# WirelessTransceiverUSB_RevA.net
KiCad netlist of a schematic drawn in EAGLE
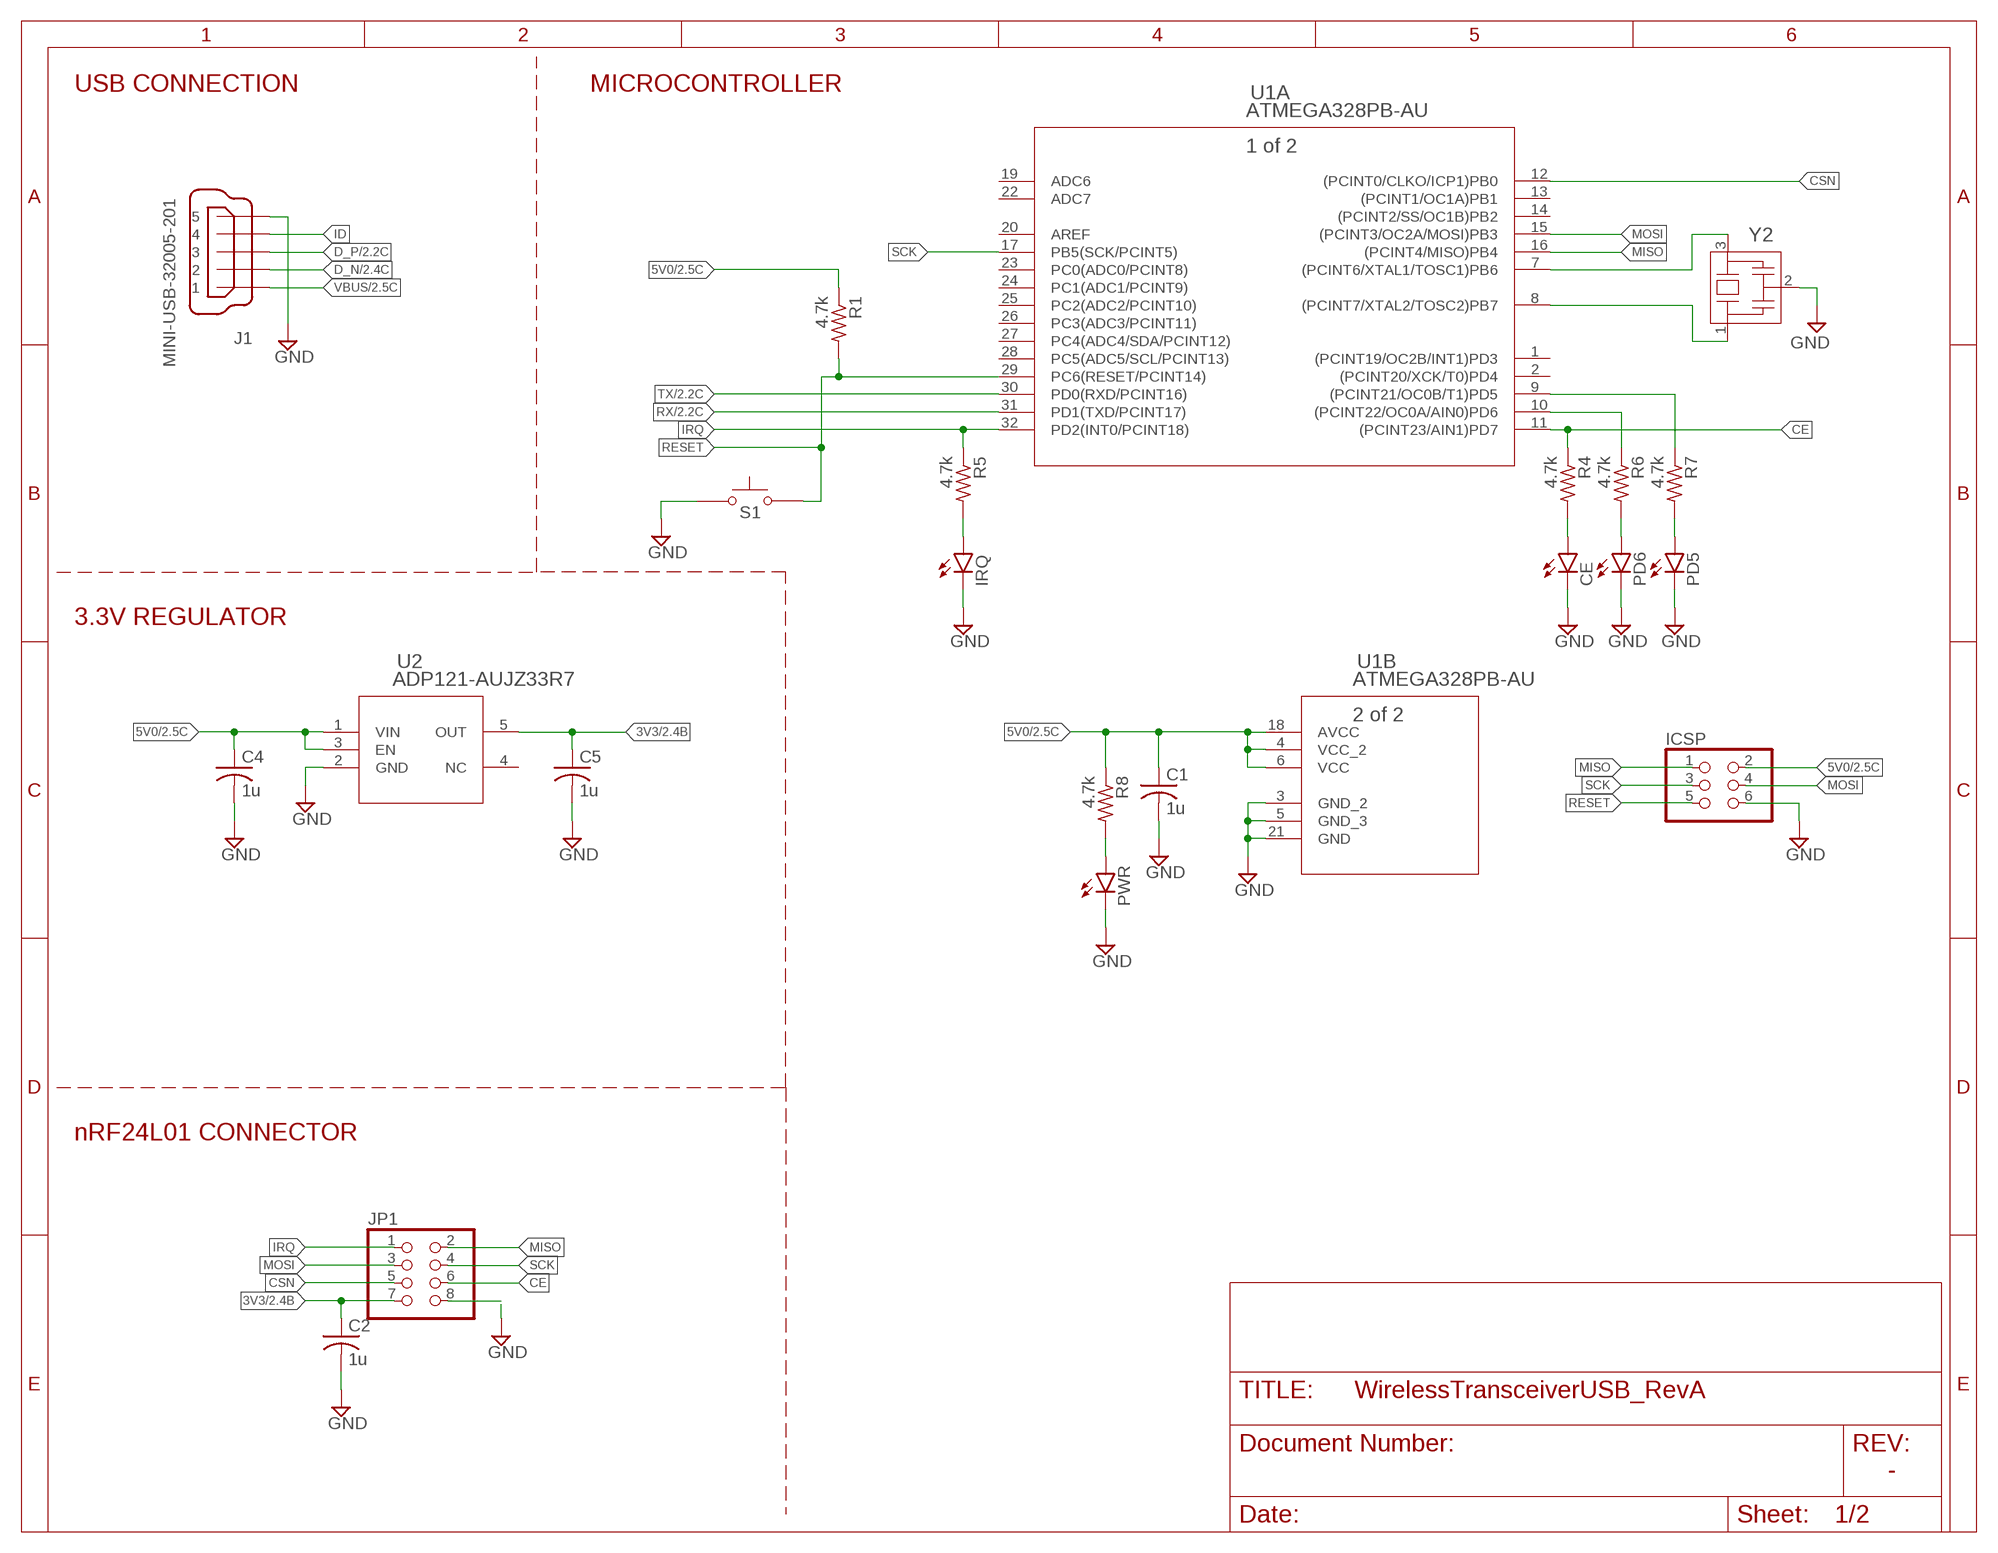
[diagram p0: schematic, sheet 1]
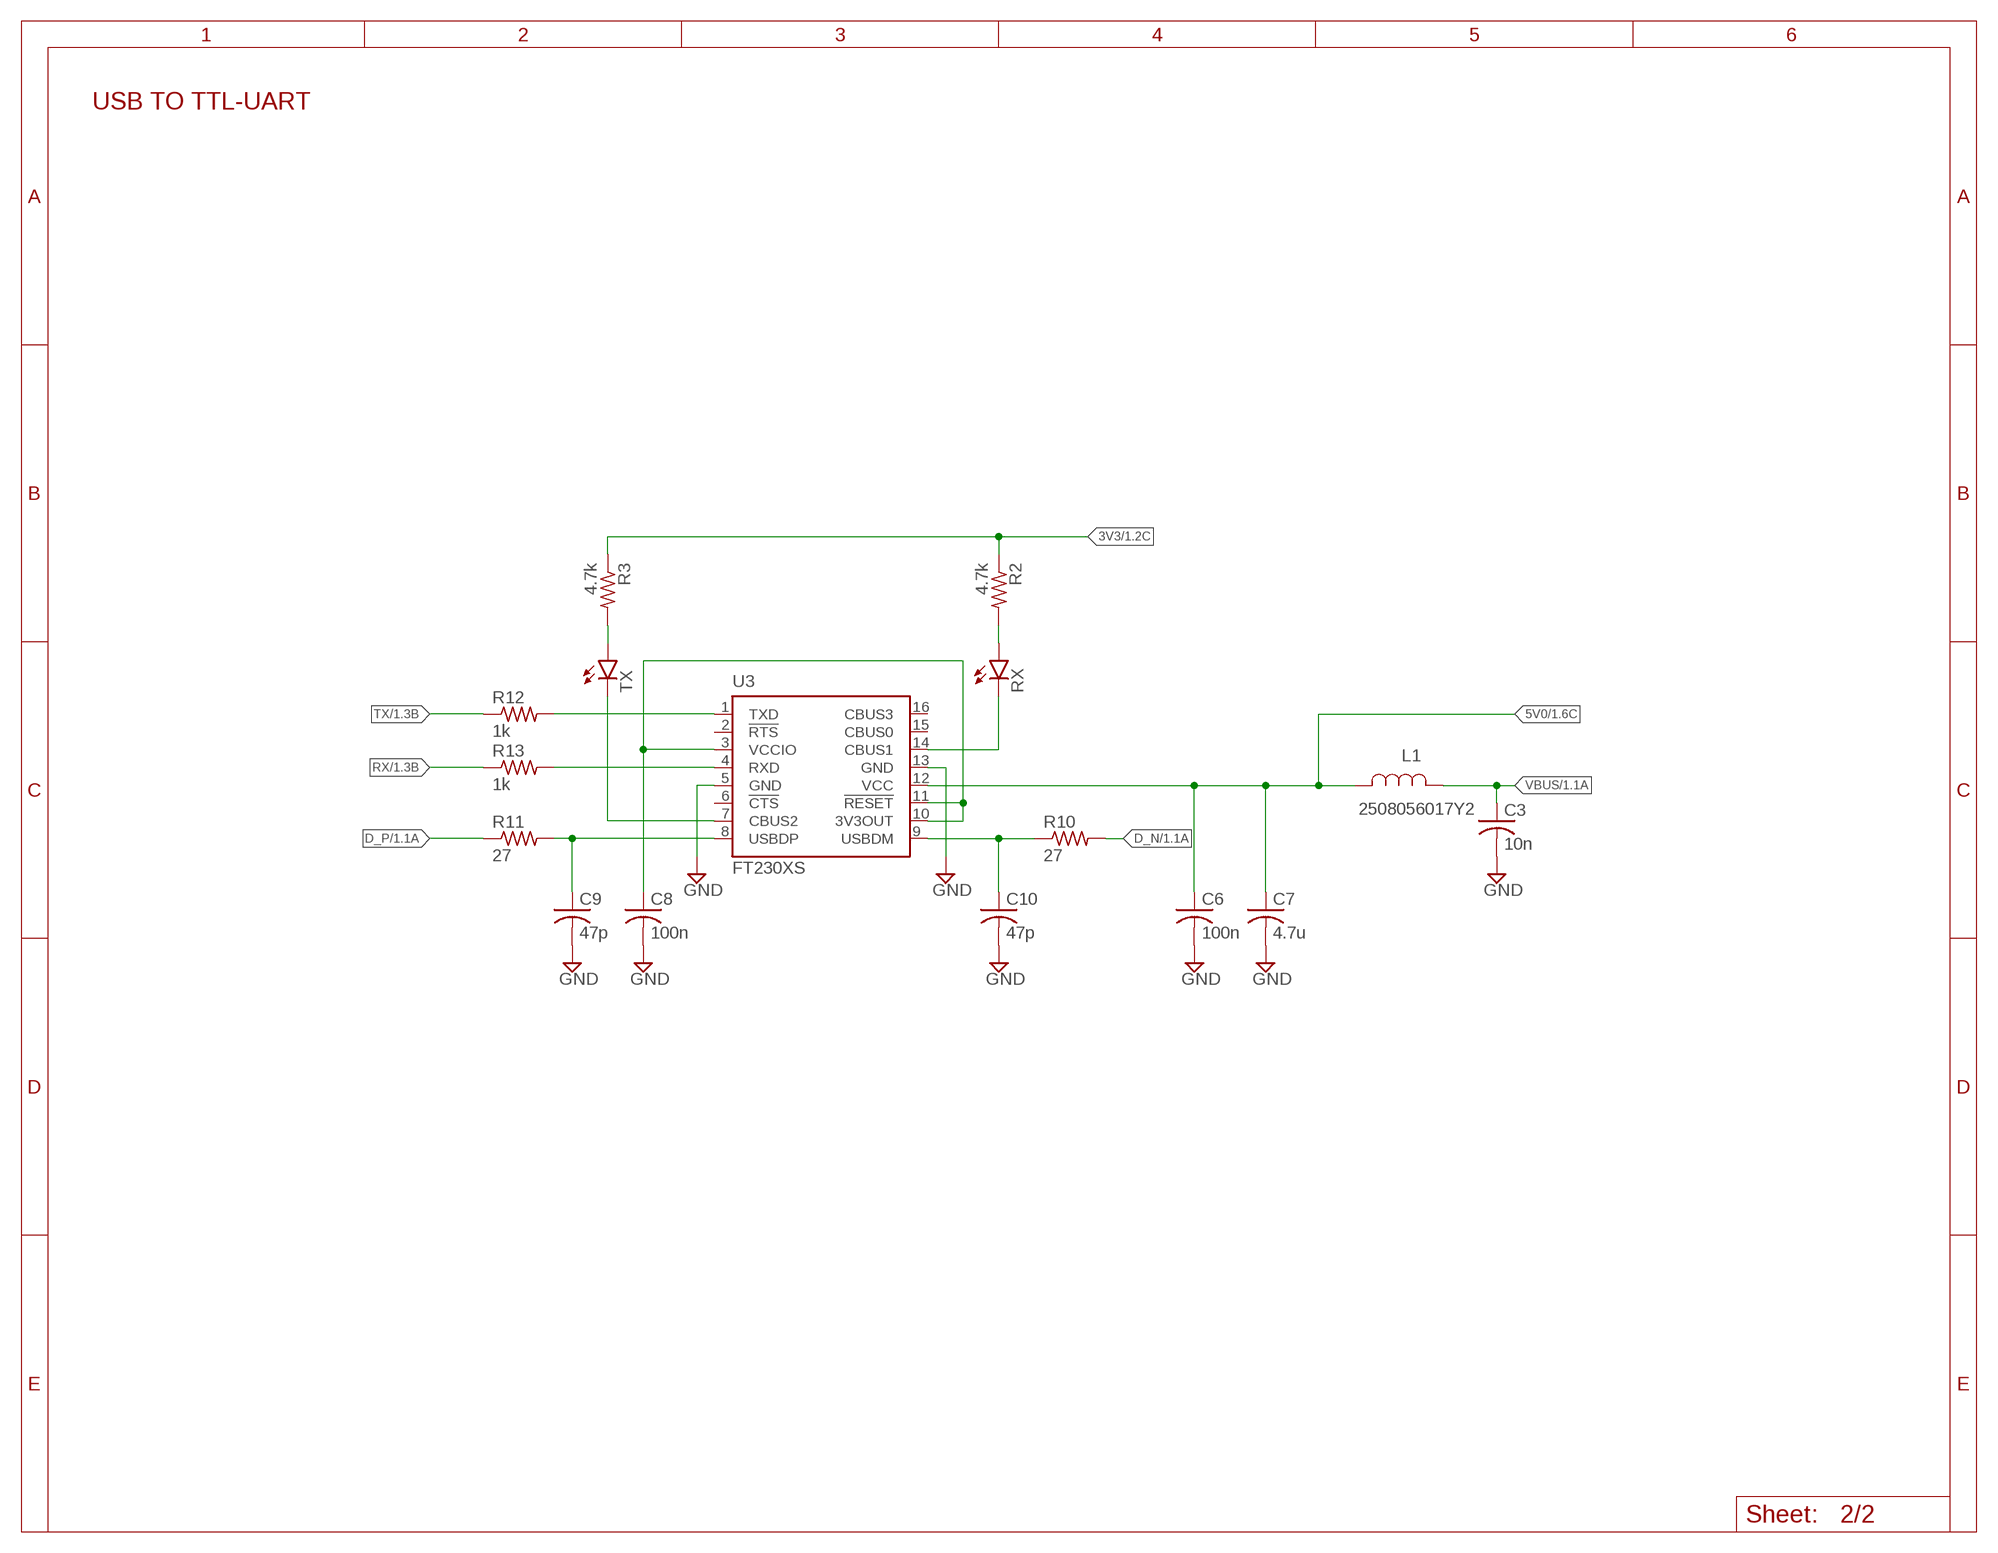
[diagram p1: schematic, sheet 2]

(export (version "E")
  (design (tool "Eeschema 10.0.6"))
  (components
    (comp (ref "C1")
      (value "1u")
      (footprint "eagle-import:C0805")
      (libsource (lib "eagle-import") (part "C-USC0805"))
    )
    (comp (ref "C2")
      (value "1u")
      (footprint "eagle-import:C0805")
      (libsource (lib "eagle-import") (part "C-USC0805"))
    )
    (comp (ref "C4")
      (value "1u")
      (footprint "eagle-import:C0805")
      (libsource (lib "eagle-import") (part "C-USC0805"))
    )
    (comp (ref "C5")
      (value "1u")
      (footprint "eagle-import:C0805")
      (libsource (lib "eagle-import") (part "C-USC0805"))
    )
    (comp (ref "CE")
      (value "LEDSML0805")
      (footprint "eagle-import:SML0805")
      (libsource (lib "eagle-import") (part "LEDSML0805"))
    )
    (comp (ref "ICSP")
      (value "PINHD-2X3")
      (footprint "eagle-import:2X03")
      (libsource (lib "eagle-import") (part "PINHD-2X3"))
    )
    (comp (ref "IRQ")
      (value "LEDSML0805")
      (footprint "eagle-import:SML0805")
      (libsource (lib "eagle-import") (part "LEDSML0805"))
    )
    (comp (ref "J1")
      (value "MINI-USB-32005-201")
      (footprint "eagle-import:32005-201")
      (libsource (lib "eagle-import") (part "MINI-USB-32005-201"))
    )
    (comp (ref "JP1")
      (value "PINHD-2X4")
      (footprint "eagle-import:2X04")
      (libsource (lib "eagle-import") (part "PINHD-2X4"))
    )
    (comp (ref "PD5")
      (value "LEDSML0805")
      (footprint "eagle-import:SML0805")
      (libsource (lib "eagle-import") (part "LEDSML0805"))
    )
    (comp (ref "PD6")
      (value "LEDSML0805")
      (footprint "eagle-import:SML0805")
      (libsource (lib "eagle-import") (part "LEDSML0805"))
    )
    (comp (ref "PWR")
      (value "LEDSML0805")
      (footprint "eagle-import:SML0805")
      (libsource (lib "eagle-import") (part "LEDSML0805"))
    )
    (comp (ref "R1")
      (value "4.7k")
      (footprint "eagle-import:R0805")
      (libsource (lib "eagle-import") (part "R-US_R0805"))
    )
    (comp (ref "R4")
      (value "4.7k")
      (footprint "eagle-import:R0805")
      (libsource (lib "eagle-import") (part "R-US_R0805"))
    )
    (comp (ref "R5")
      (value "4.7k")
      (footprint "eagle-import:R0805")
      (libsource (lib "eagle-import") (part "R-US_R0805"))
    )
    (comp (ref "R6")
      (value "4.7k")
      (footprint "eagle-import:R0805")
      (libsource (lib "eagle-import") (part "R-US_R0805"))
    )
    (comp (ref "R7")
      (value "4.7k")
      (footprint "eagle-import:R0805")
      (libsource (lib "eagle-import") (part "R-US_R0805"))
    )
    (comp (ref "R8")
      (value "4.7k")
      (footprint "eagle-import:R0805")
      (libsource (lib "eagle-import") (part "R-US_R0805"))
    )
    (comp (ref "S1")
      (value "TL3315NF100Q")
      (footprint "eagle-import:SW_TL3315NF100Q")
      (fields (field (name "MF") "E-Switch"))
      (libsource (lib "eagle-import") (part "TL3315NF100Q"))
    )
    (comp (ref "U1")
      (value "ATMEGA328PB-AU")
      (footprint "eagle-import:32A_MCH")
      (fields (field (name "COPYRIGHT") "Copyright (C) 2023 Ultra Librarian. All rights reserved."))
      (libsource (lib "eagle-import") (part "ATMEGA328PB-AU"))
    )
    (comp (ref "U2")
      (value "ADP121-AUJZ33R7")
      (footprint "eagle-import:UJ_5_ADI")
      (fields (field (name "COPYRIGHT") "Copyright (C) 2023 Ultra Librarian. All rights reserved."))
      (libsource (lib "eagle-import") (part "ADP121-AUJZ33R7"))
    )
    (comp (ref "Y2")
      (value "CSTNE16M0V530000R0")
      (footprint "eagle-import:CSTNE16M0V530000R0_MUR")
      (fields (field (name "COPYRIGHT") "Copyright (C) 2023 Ultra Librarian. All rights reserved."))
      (libsource (lib "eagle-import") (part "CSTNE16M0V530000R0"))
    )
    (comp (ref "C3")
      (value "10n")
      (footprint "eagle-import:C0805")
      (libsource (lib "eagle-import") (part "C-USC0805"))
    )
    (comp (ref "C6")
      (value "100n")
      (footprint "eagle-import:C0805")
      (libsource (lib "eagle-import") (part "C-USC0805"))
    )
    (comp (ref "C7")
      (value "4.7u")
      (footprint "eagle-import:C0805")
      (libsource (lib "eagle-import") (part "C-USC0805"))
    )
    (comp (ref "C8")
      (value "100n")
      (footprint "eagle-import:C0805")
      (libsource (lib "eagle-import") (part "C-USC0805"))
    )
    (comp (ref "C9")
      (value "47p")
      (footprint "eagle-import:C0603")
      (libsource (lib "eagle-import") (part "C-USC0603"))
    )
    (comp (ref "C10")
      (value "47p")
      (footprint "eagle-import:C0603")
      (libsource (lib "eagle-import") (part "C-USC0603"))
    )
    (comp (ref "L1")
      (value "2508056017Y2")
      (footprint "eagle-import:IND_25_0805_FRT")
      (fields (field (name "COPYRIGHT") "Copyright (C) 2023 Ultra Librarian. All rights reserved."))
      (libsource (lib "eagle-import") (part "2508056017Y2"))
    )
    (comp (ref "R2")
      (value "4.7k")
      (footprint "eagle-import:R0805")
      (libsource (lib "eagle-import") (part "R-US_R0805"))
    )
    (comp (ref "R3")
      (value "4.7k")
      (footprint "eagle-import:R0805")
      (libsource (lib "eagle-import") (part "R-US_R0805"))
    )
    (comp (ref "R10")
      (value "27")
      (footprint "eagle-import:R0603")
      (libsource (lib "eagle-import") (part "R-US_R0603"))
    )
    (comp (ref "R11")
      (value "27")
      (footprint "eagle-import:R0603")
      (libsource (lib "eagle-import") (part "R-US_R0603"))
    )
    (comp (ref "R12")
      (value "1k")
      (footprint "eagle-import:R0805")
      (libsource (lib "eagle-import") (part "R-US_R0805"))
    )
    (comp (ref "R13")
      (value "1k")
      (footprint "eagle-import:R0805")
      (libsource (lib "eagle-import") (part "R-US_R0805"))
    )
    (comp (ref "RX")
      (value "LEDSML0805")
      (footprint "eagle-import:SML0805")
      (libsource (lib "eagle-import") (part "LEDSML0805"))
    )
    (comp (ref "TX")
      (value "LEDSML0805")
      (footprint "eagle-import:SML0805")
      (libsource (lib "eagle-import") (part "LEDSML0805"))
    )
    (comp (ref "U3")
      (value "FT230XS")
      (footprint "eagle-import:SSOP16")
      (libsource (lib "eagle-import") (part "FT230XS"))
    )
  )
  (nets
    (net (code "1") (name "3V3") (class "Default")
      (node (ref "C2") (pin "1") (pinfunction "1_1") (pintype "passive"))
      (node (ref "C5") (pin "1") (pinfunction "1_1") (pintype "passive"))
      (node (ref "JP1") (pin "7") (pinfunction "7_7") (pintype "passive"))
      (node (ref "R2") (pin "1") (pinfunction "1_1") (pintype "passive"))
      (node (ref "R3") (pin "1") (pinfunction "1_1") (pintype "passive"))
      (node (ref "U2") (pin "5") (pinfunction "OUT_5") (pintype "output"))
    )
    (net (code "2") (name "5V0") (class "Default")
      (node (ref "C1") (pin "1") (pinfunction "1_1") (pintype "passive"))
      (node (ref "C4") (pin "1") (pinfunction "1_1") (pintype "passive"))
      (node (ref "C6") (pin "1") (pinfunction "1_1") (pintype "passive"))
      (node (ref "C7") (pin "1") (pinfunction "1_1") (pintype "passive"))
      (node (ref "ICSP") (pin "2") (pinfunction "2_2") (pintype "passive"))
      (node (ref "L1") (pin "2") (pinfunction "2_2") (pintype "passive"))
      (node (ref "R1") (pin "1") (pinfunction "1_1") (pintype "passive"))
      (node (ref "R8") (pin "1") (pinfunction "1_1") (pintype "passive"))
      (node (ref "U1") (pin "18") (pinfunction "AVCC_18") (pintype "power_in"))
      (node (ref "U1") (pin "4") (pinfunction "VCC_2_4") (pintype "power_in"))
      (node (ref "U1") (pin "6") (pinfunction "VCC_6") (pintype "power_in"))
      (node (ref "U2") (pin "1") (pinfunction "VIN_1") (pintype "input"))
      (node (ref "U2") (pin "3") (pinfunction "EN_3") (pintype "input"))
      (node (ref "U3") (pin "12") (pinfunction "VCC_12") (pintype "power_in"))
    )
    (net (code "3") (name "CE") (class "Default")
      (node (ref "JP1") (pin "6") (pinfunction "6_6") (pintype "passive"))
      (node (ref "R4") (pin "1") (pinfunction "1_1") (pintype "passive"))
      (node (ref "U1") (pin "11") (pinfunction "(PCINT23/AIN1)PD7_11") (pintype "bidirectional"))
    )
    (net (code "4") (name "CSN") (class "Default")
      (node (ref "JP1") (pin "5") (pinfunction "5_5") (pintype "passive"))
      (node (ref "U1") (pin "12") (pinfunction "(PCINT0/CLKO/ICP1)PB0_12") (pintype "bidirectional"))
    )
    (net (code "5") (name "D_N") (class "Default")
      (node (ref "J1") (pin "2") (pinfunction "2_2") (pintype "passive"))
      (node (ref "R10") (pin "2") (pinfunction "2_2") (pintype "passive"))
    )
    (net (code "6") (name "D_P") (class "Default")
      (node (ref "J1") (pin "3") (pinfunction "3_3") (pintype "passive"))
      (node (ref "R11") (pin "1") (pinfunction "1_1") (pintype "passive"))
    )
    (net (code "7") (name "GND") (class "Default")
      (node (ref "C1") (pin "2") (pinfunction "2_2") (pintype "passive"))
      (node (ref "C10") (pin "2") (pinfunction "2_2") (pintype "passive"))
      (node (ref "C2") (pin "2") (pinfunction "2_2") (pintype "passive"))
      (node (ref "C3") (pin "2") (pinfunction "2_2") (pintype "passive"))
      (node (ref "C4") (pin "2") (pinfunction "2_2") (pintype "passive"))
      (node (ref "C5") (pin "2") (pinfunction "2_2") (pintype "passive"))
      (node (ref "C6") (pin "2") (pinfunction "2_2") (pintype "passive"))
      (node (ref "C7") (pin "2") (pinfunction "2_2") (pintype "passive"))
      (node (ref "C8") (pin "2") (pinfunction "2_2") (pintype "passive"))
      (node (ref "C9") (pin "2") (pinfunction "2_2") (pintype "passive"))
      (node (ref "CE") (pin "C") (pinfunction "C_C") (pintype "passive"))
      (node (ref "ICSP") (pin "6") (pinfunction "6_6") (pintype "passive"))
      (node (ref "IRQ") (pin "C") (pinfunction "C_C") (pintype "passive"))
      (node (ref "J1") (pin "5") (pinfunction "5_5") (pintype "passive"))
      (node (ref "JP1") (pin "8") (pinfunction "8_8") (pintype "passive"))
      (node (ref "PD5") (pin "C") (pinfunction "C_C") (pintype "passive"))
      (node (ref "PD6") (pin "C") (pinfunction "C_C") (pintype "passive"))
      (node (ref "PWR") (pin "C") (pinfunction "C_C") (pintype "passive"))
      (node (ref "S1") (pin "1") (pinfunction "1_1") (pintype "passive"))
      (node (ref "S1") (pin "2") (pinfunction "1_2") (pintype "passive"))
      (node (ref "U1") (pin "21") (pinfunction "GND_21") (pintype "power_in"))
      (node (ref "U1") (pin "3") (pinfunction "GND_2_3") (pintype "power_in"))
      (node (ref "U1") (pin "5") (pinfunction "GND_3_5") (pintype "power_in"))
      (node (ref "U2") (pin "2") (pinfunction "GND_2") (pintype "power_in"))
      (node (ref "U3") (pin "13") (pinfunction "GND_13") (pintype "power_in"))
      (node (ref "U3") (pin "5") (pinfunction "GND_5") (pintype "power_in"))
      (node (ref "Y2") (pin "2") (pinfunction "2_2") (pintype "passive"))
    )
    (net (code "8") (name "ID") (class "Default")
      (node (ref "J1") (pin "4") (pinfunction "4_4") (pintype "passive"))
    )
    (net (code "9") (name "IRQ") (class "Default")
      (node (ref "JP1") (pin "1") (pinfunction "1_1") (pintype "passive"))
      (node (ref "R5") (pin "1") (pinfunction "1_1") (pintype "passive"))
      (node (ref "U1") (pin "32") (pinfunction "PD2(INT0/PCINT18)_32") (pintype "bidirectional"))
    )
    (net (code "10") (name "MISO") (class "Default")
      (node (ref "ICSP") (pin "1") (pinfunction "1_1") (pintype "passive"))
      (node (ref "JP1") (pin "2") (pinfunction "2_2") (pintype "passive"))
      (node (ref "U1") (pin "16") (pinfunction "(PCINT4/MISO)PB4_16") (pintype "bidirectional"))
    )
    (net (code "11") (name "MOSI") (class "Default")
      (node (ref "ICSP") (pin "4") (pinfunction "4_4") (pintype "passive"))
      (node (ref "JP1") (pin "3") (pinfunction "3_3") (pintype "passive"))
      (node (ref "U1") (pin "15") (pinfunction "(PCINT3/OC2A/MOSI)PB3_15") (pintype "bidirectional"))
    )
    (net (code "12") (name "Net-(CE-PadA)") (class "Default")
      (node (ref "CE") (pin "A") (pinfunction "A_A") (pintype "passive"))
      (node (ref "R4") (pin "2") (pinfunction "2_2") (pintype "passive"))
    )
    (net (code "13") (name "Net-(IRQ-PadA)") (class "Default")
      (node (ref "IRQ") (pin "A") (pinfunction "A_A") (pintype "passive"))
      (node (ref "R5") (pin "2") (pinfunction "2_2") (pintype "passive"))
    )
    (net (code "14") (name "Net-(PD5-PadA)") (class "Default")
      (node (ref "PD5") (pin "A") (pinfunction "A_A") (pintype "passive"))
      (node (ref "R7") (pin "2") (pinfunction "2_2") (pintype "passive"))
    )
    (net (code "15") (name "Net-(PD6-PadA)") (class "Default")
      (node (ref "PD6") (pin "A") (pinfunction "A_A") (pintype "passive"))
      (node (ref "R6") (pin "2") (pinfunction "2_2") (pintype "passive"))
    )
    (net (code "16") (name "Net-(PWR-PadA)") (class "Default")
      (node (ref "PWR") (pin "A") (pinfunction "A_A") (pintype "passive"))
      (node (ref "R8") (pin "2") (pinfunction "2_2") (pintype "passive"))
    )
    (net (code "17") (name "Net-(R2-Pad2)") (class "Default")
      (node (ref "R2") (pin "2") (pinfunction "2_2") (pintype "passive"))
      (node (ref "RX") (pin "A") (pinfunction "A_A") (pintype "passive"))
    )
    (net (code "18") (name "Net-(R3-Pad2)") (class "Default")
      (node (ref "R3") (pin "2") (pinfunction "2_2") (pintype "passive"))
      (node (ref "TX") (pin "A") (pinfunction "A_A") (pintype "passive"))
    )
    (net (code "19") (name "Net-(U1A-(PCINT6{slash}XTAL1{slash}TOSC1)PB6)") (class "Default")
      (node (ref "U1") (pin "7") (pinfunction "(PCINT6/XTAL1/TOSC1)PB6_7") (pintype "bidirectional"))
      (node (ref "Y2") (pin "3") (pinfunction "3_3") (pintype "output"))
    )
    (net (code "20") (name "Net-(U1A-(PCINT7{slash}XTAL2{slash}TOSC2)PB7)") (class "Default")
      (node (ref "U1") (pin "8") (pinfunction "(PCINT7/XTAL2/TOSC2)PB7_8") (pintype "bidirectional"))
      (node (ref "Y2") (pin "1") (pinfunction "1_1") (pintype "input"))
    )
    (net (code "21") (name "Net-(U1A-(PCINT21{slash}OC0B{slash}T1)PD5)") (class "Default")
      (node (ref "R7") (pin "1") (pinfunction "1_1") (pintype "passive"))
      (node (ref "U1") (pin "9") (pinfunction "(PCINT21/OC0B/T1)PD5_9") (pintype "bidirectional"))
    )
    (net (code "22") (name "Net-(U1A-(PCINT22{slash}OC0A{slash}AIN0)PD6)") (class "Default")
      (node (ref "R6") (pin "1") (pinfunction "1_1") (pintype "passive"))
      (node (ref "U1") (pin "10") (pinfunction "(PCINT22/OC0A/AIN0)PD6_10") (pintype "bidirectional"))
    )
    (net (code "23") (name "Net-(U3-3V3OUT)") (class "Default")
      (node (ref "C8") (pin "1") (pinfunction "1_1") (pintype "passive"))
      (node (ref "U3") (pin "10") (pinfunction "3V3OUT_10") (pintype "output"))
      (node (ref "U3") (pin "11") (pinfunction "~{RESET}_11") (pintype "input"))
      (node (ref "U3") (pin "3") (pinfunction "VCCIO_3") (pintype "power_in"))
    )
    (net (code "24") (name "Net-(U3-CBUS1)") (class "Default")
      (node (ref "RX") (pin "C") (pinfunction "C_C") (pintype "passive"))
      (node (ref "U3") (pin "14") (pinfunction "CBUS1_14") (pintype "bidirectional"))
    )
    (net (code "25") (name "Net-(U3-CBUS2)") (class "Default")
      (node (ref "TX") (pin "C") (pinfunction "C_C") (pintype "passive"))
      (node (ref "U3") (pin "7") (pinfunction "CBUS2_7") (pintype "bidirectional"))
    )
    (net (code "26") (name "Net-(U3-RXD)") (class "Default")
      (node (ref "R13") (pin "2") (pinfunction "2_2") (pintype "passive"))
      (node (ref "U3") (pin "4") (pinfunction "RXD_4") (pintype "input"))
    )
    (net (code "27") (name "Net-(U3-TXD)") (class "Default")
      (node (ref "R12") (pin "2") (pinfunction "2_2") (pintype "passive"))
      (node (ref "U3") (pin "1") (pinfunction "TXD_1") (pintype "output"))
    )
    (net (code "28") (name "Net-(U3-USBDM)") (class "Default")
      (node (ref "C10") (pin "1") (pinfunction "1_1") (pintype "passive"))
      (node (ref "R10") (pin "1") (pinfunction "1_1") (pintype "passive"))
      (node (ref "U3") (pin "9") (pinfunction "USBDM_9") (pintype "input"))
    )
    (net (code "29") (name "Net-(U3-USBDP)") (class "Default")
      (node (ref "C9") (pin "1") (pinfunction "1_1") (pintype "passive"))
      (node (ref "R11") (pin "2") (pinfunction "2_2") (pintype "passive"))
      (node (ref "U3") (pin "8") (pinfunction "USBDP_8") (pintype "input"))
    )
    (net (code "30") (name "RESET") (class "Default")
      (node (ref "ICSP") (pin "5") (pinfunction "5_5") (pintype "passive"))
      (node (ref "R1") (pin "2") (pinfunction "2_2") (pintype "passive"))
      (node (ref "S1") (pin "3") (pinfunction "3_3") (pintype "passive"))
      (node (ref "S1") (pin "4") (pinfunction "3_4") (pintype "passive"))
      (node (ref "U1") (pin "29") (pinfunction "PC6(RESET/PCINT14)_29") (pintype "bidirectional"))
    )
    (net (code "31") (name "RX") (class "Default")
      (node (ref "R13") (pin "1") (pinfunction "1_1") (pintype "passive"))
      (node (ref "U1") (pin "31") (pinfunction "PD1(TXD/PCINT17)_31") (pintype "bidirectional"))
    )
    (net (code "32") (name "SCK") (class "Default")
      (node (ref "ICSP") (pin "3") (pinfunction "3_3") (pintype "passive"))
      (node (ref "JP1") (pin "4") (pinfunction "4_4") (pintype "passive"))
      (node (ref "U1") (pin "17") (pinfunction "PB5(SCK/PCINT5)_17") (pintype "bidirectional"))
    )
    (net (code "33") (name "TX") (class "Default")
      (node (ref "R12") (pin "1") (pinfunction "1_1") (pintype "passive"))
      (node (ref "U1") (pin "30") (pinfunction "PD0(RXD/PCINT16)_30") (pintype "bidirectional"))
    )
    (net (code "34") (name "VBUS") (class "Default")
      (node (ref "C3") (pin "1") (pinfunction "1_1") (pintype "passive"))
      (node (ref "J1") (pin "1") (pinfunction "1_1") (pintype "passive"))
      (node (ref "L1") (pin "1") (pinfunction "1_1") (pintype "passive"))
    )
    (net (code "35") (name "unconnected-(U1A-(PCINT1{slash}OC1A)PB1-Pad13)") (class "Default")
      (node (ref "U1") (pin "13") (pinfunction "(PCINT1/OC1A)PB1_13") (pintype "bidirectional"))
    )
    (net (code "36") (name "unconnected-(U1A-(PCINT2{slash}SS{slash}OC1B)PB2-Pad14)") (class "Default")
      (node (ref "U1") (pin "14") (pinfunction "(PCINT2/SS/OC1B)PB2_14") (pintype "bidirectional"))
    )
    (net (code "37") (name "unconnected-(U1A-(PCINT19{slash}OC2B{slash}INT1)PD3-Pad1)") (class "Default")
      (node (ref "U1") (pin "1") (pinfunction "(PCINT19/OC2B/INT1)PD3_1") (pintype "bidirectional"))
    )
    (net (code "38") (name "unconnected-(U1A-(PCINT20{slash}XCK{slash}T0)PD4-Pad2)") (class "Default")
      (node (ref "U1") (pin "2") (pinfunction "(PCINT20/XCK/T0)PD4_2") (pintype "bidirectional"))
    )
    (net (code "39") (name "unconnected-(U1A-ADC6-Pad19)") (class "Default")
      (node (ref "U1") (pin "19") (pinfunction "ADC6_19") (pintype "input"))
    )
    (net (code "40") (name "unconnected-(U1A-ADC7-Pad22)") (class "Default")
      (node (ref "U1") (pin "22") (pinfunction "ADC7_22") (pintype "input"))
    )
    (net (code "41") (name "unconnected-(U1A-AREF-Pad20)") (class "Default")
      (node (ref "U1") (pin "20") (pinfunction "AREF_20") (pintype "passive"))
    )
    (net (code "42") (name "unconnected-(U1A-PC0(ADC0{slash}PCINT8)-Pad23)") (class "Default")
      (node (ref "U1") (pin "23") (pinfunction "PC0(ADC0/PCINT8)_23") (pintype "bidirectional"))
    )
    (net (code "43") (name "unconnected-(U1A-PC1(ADC1{slash}PCINT9)-Pad24)") (class "Default")
      (node (ref "U1") (pin "24") (pinfunction "PC1(ADC1/PCINT9)_24") (pintype "bidirectional"))
    )
    (net (code "44") (name "unconnected-(U1A-PC2(ADC2{slash}PCINT10)-Pad25)") (class "Default")
      (node (ref "U1") (pin "25") (pinfunction "PC2(ADC2/PCINT10)_25") (pintype "bidirectional"))
    )
    (net (code "45") (name "unconnected-(U1A-PC3(ADC3{slash}PCINT11)-Pad26)") (class "Default")
      (node (ref "U1") (pin "26") (pinfunction "PC3(ADC3/PCINT11)_26") (pintype "bidirectional"))
    )
    (net (code "46") (name "unconnected-(U1A-PC4(ADC4{slash}SDA{slash}PCINT12)-Pad27)") (class "Default")
      (node (ref "U1") (pin "27") (pinfunction "PC4(ADC4/SDA/PCINT12)_27") (pintype "bidirectional"))
    )
    (net (code "47") (name "unconnected-(U1A-PC5(ADC5{slash}SCL{slash}PCINT13)-Pad28)") (class "Default")
      (node (ref "U1") (pin "28") (pinfunction "PC5(ADC5/SCL/PCINT13)_28") (pintype "bidirectional"))
    )
    (net (code "48") (name "unconnected-(U2-NC-Pad4)") (class "Default")
      (node (ref "U2") (pin "4") (pinfunction "NC_4") (pintype "no_connect"))
    )
    (net (code "49") (name "unconnected-(U3-CBUS0-Pad15)") (class "Default")
      (node (ref "U3") (pin "15") (pinfunction "CBUS0_15") (pintype "bidirectional"))
    )
    (net (code "50") (name "unconnected-(U3-CBUS3-Pad16)") (class "Default")
      (node (ref "U3") (pin "16") (pinfunction "CBUS3_16") (pintype "bidirectional"))
    )
    (net (code "51") (name "unconnected-(U3-~{CTS}-Pad6)") (class "Default")
      (node (ref "U3") (pin "6") (pinfunction "~{CTS}_6") (pintype "input"))
    )
    (net (code "52") (name "unconnected-(U3-~{RTS}-Pad2)") (class "Default")
      (node (ref "U3") (pin "2") (pinfunction "~{RTS}_2") (pintype "output"))
    )
  )
)
